# untitled.net
KiCad netlist of a schematic drawn in EAGLE
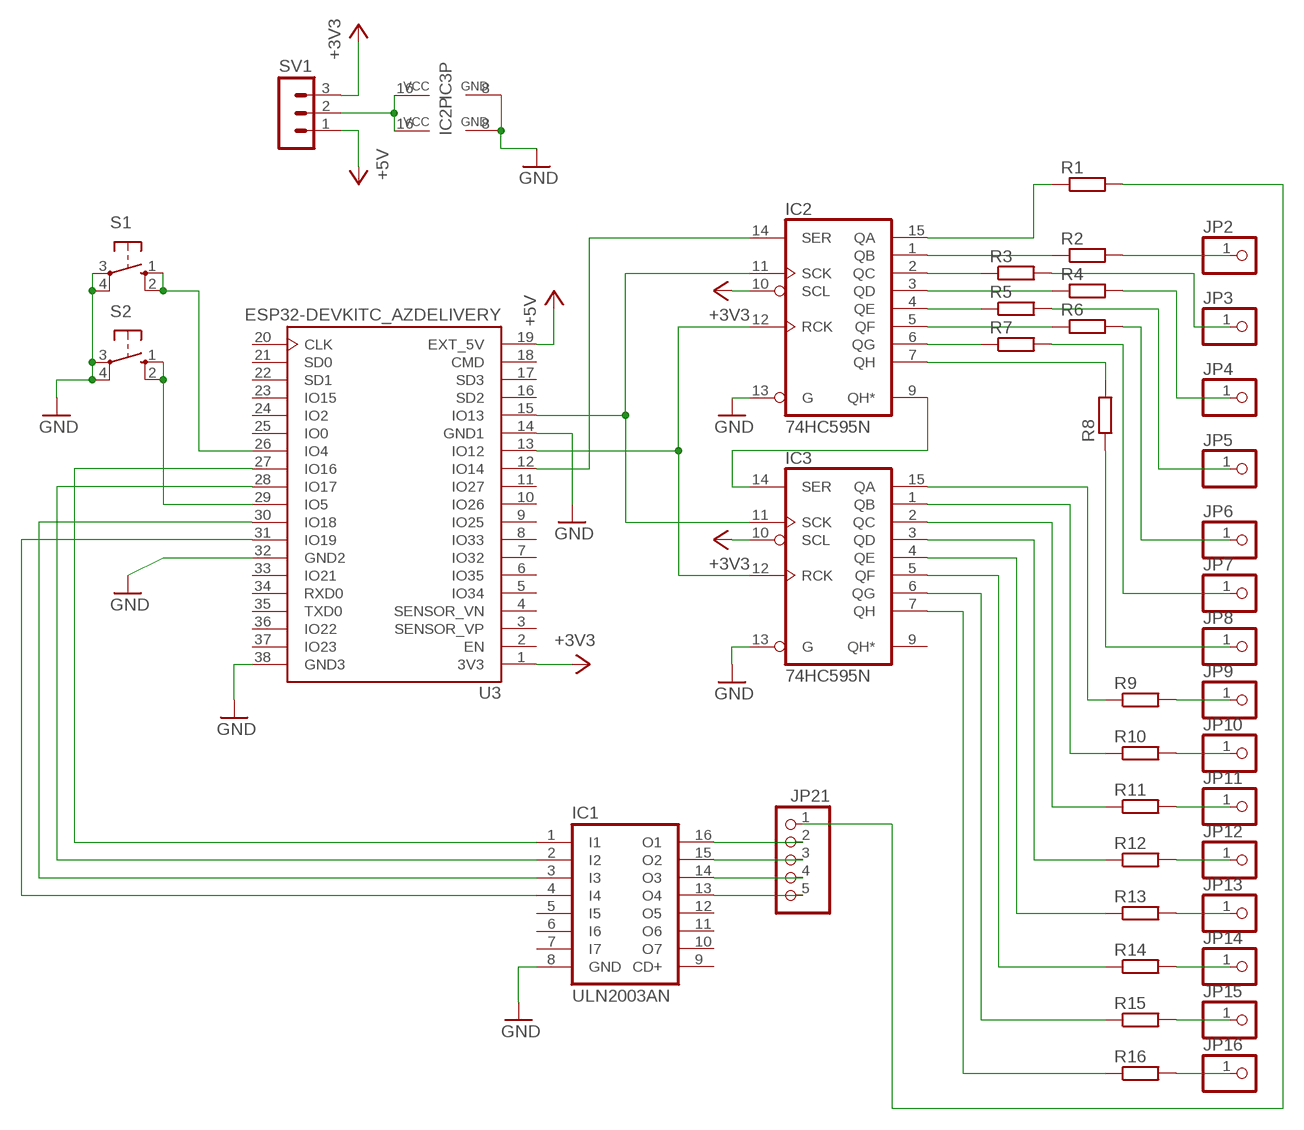
[diagram p0: schematic, sheet 1]

(export (version "E")
  (design (tool "Eeschema 10.0.6"))
  (components
    (comp (ref "IC1")
      (value "ULN2003AN")
      (footprint "eagle-import:DIL16")
      (libsource (lib "eagle-import") (part "ULN2003AN"))
    )
    (comp (ref "IC2")
      (value "74HC595N")
      (footprint "eagle-import:DIL16")
      (libsource (lib "eagle-import") (part "74595NHC"))
    )
    (comp (ref "IC3")
      (value "74HC595N")
      (footprint "eagle-import:DIL16")
      (libsource (lib "eagle-import") (part "74595NHC"))
    )
    (comp (ref "JP2")
      (value "PINHD-1X1")
      (footprint "eagle-import:1X01")
      (libsource (lib "eagle-import") (part "PINHD-1X1"))
    )
    (comp (ref "JP3")
      (value "PINHD-1X1")
      (footprint "eagle-import:1X01")
      (libsource (lib "eagle-import") (part "PINHD-1X1"))
    )
    (comp (ref "JP4")
      (value "PINHD-1X1")
      (footprint "eagle-import:1X01")
      (libsource (lib "eagle-import") (part "PINHD-1X1"))
    )
    (comp (ref "JP5")
      (value "PINHD-1X1")
      (footprint "eagle-import:1X01")
      (libsource (lib "eagle-import") (part "PINHD-1X1"))
    )
    (comp (ref "JP6")
      (value "PINHD-1X1")
      (footprint "eagle-import:1X01")
      (libsource (lib "eagle-import") (part "PINHD-1X1"))
    )
    (comp (ref "JP7")
      (value "PINHD-1X1")
      (footprint "eagle-import:1X01")
      (libsource (lib "eagle-import") (part "PINHD-1X1"))
    )
    (comp (ref "JP8")
      (value "PINHD-1X1")
      (footprint "eagle-import:1X01")
      (libsource (lib "eagle-import") (part "PINHD-1X1"))
    )
    (comp (ref "JP9")
      (value "PINHD-1X1")
      (footprint "eagle-import:1X01")
      (libsource (lib "eagle-import") (part "PINHD-1X1"))
    )
    (comp (ref "JP10")
      (value "PINHD-1X1")
      (footprint "eagle-import:1X01")
      (libsource (lib "eagle-import") (part "PINHD-1X1"))
    )
    (comp (ref "JP11")
      (value "PINHD-1X1")
      (footprint "eagle-import:1X01")
      (libsource (lib "eagle-import") (part "PINHD-1X1"))
    )
    (comp (ref "JP12")
      (value "PINHD-1X1")
      (footprint "eagle-import:1X01")
      (libsource (lib "eagle-import") (part "PINHD-1X1"))
    )
    (comp (ref "JP13")
      (value "PINHD-1X1")
      (footprint "eagle-import:1X01")
      (libsource (lib "eagle-import") (part "PINHD-1X1"))
    )
    (comp (ref "JP14")
      (value "PINHD-1X1")
      (footprint "eagle-import:1X01")
      (libsource (lib "eagle-import") (part "PINHD-1X1"))
    )
    (comp (ref "JP15")
      (value "PINHD-1X1")
      (footprint "eagle-import:1X01")
      (libsource (lib "eagle-import") (part "PINHD-1X1"))
    )
    (comp (ref "JP16")
      (value "PINHD-1X1")
      (footprint "eagle-import:1X01")
      (libsource (lib "eagle-import") (part "PINHD-1X1"))
    )
    (comp (ref "JP21")
      (value "PINHD-1X5")
      (footprint "eagle-import:1X05")
      (libsource (lib "eagle-import") (part "PINHD-1X5"))
    )
    (comp (ref "R1")
      (value "R-EU_0207/10")
      (footprint "eagle-import:0207_10")
      (libsource (lib "eagle-import") (part "R-EU_0207/10"))
    )
    (comp (ref "R2")
      (value "R-EU_0207/10")
      (footprint "eagle-import:0207_10")
      (libsource (lib "eagle-import") (part "R-EU_0207/10"))
    )
    (comp (ref "R3")
      (value "R-EU_0207/10")
      (footprint "eagle-import:0207_10")
      (libsource (lib "eagle-import") (part "R-EU_0207/10"))
    )
    (comp (ref "R4")
      (value "R-EU_0207/10")
      (footprint "eagle-import:0207_10")
      (libsource (lib "eagle-import") (part "R-EU_0207/10"))
    )
    (comp (ref "R5")
      (value "R-EU_0207/10")
      (footprint "eagle-import:0207_10")
      (libsource (lib "eagle-import") (part "R-EU_0207/10"))
    )
    (comp (ref "R6")
      (value "R-EU_0207/10")
      (footprint "eagle-import:0207_10")
      (libsource (lib "eagle-import") (part "R-EU_0207/10"))
    )
    (comp (ref "R7")
      (value "R-EU_0207/10")
      (footprint "eagle-import:0207_10")
      (libsource (lib "eagle-import") (part "R-EU_0207/10"))
    )
    (comp (ref "R8")
      (value "R-EU_0207/10")
      (footprint "eagle-import:0207_10")
      (libsource (lib "eagle-import") (part "R-EU_0207/10"))
    )
    (comp (ref "R9")
      (value "R-EU_0207/10")
      (footprint "eagle-import:0207_10")
      (libsource (lib "eagle-import") (part "R-EU_0207/10"))
    )
    (comp (ref "R10")
      (value "R-EU_0207/10")
      (footprint "eagle-import:0207_10")
      (libsource (lib "eagle-import") (part "R-EU_0207/10"))
    )
    (comp (ref "R11")
      (value "R-EU_0207/10")
      (footprint "eagle-import:0207_10")
      (libsource (lib "eagle-import") (part "R-EU_0207/10"))
    )
    (comp (ref "R12")
      (value "R-EU_0207/10")
      (footprint "eagle-import:0207_10")
      (libsource (lib "eagle-import") (part "R-EU_0207/10"))
    )
    (comp (ref "R13")
      (value "R-EU_0207/10")
      (footprint "eagle-import:0207_10")
      (libsource (lib "eagle-import") (part "R-EU_0207/10"))
    )
    (comp (ref "R14")
      (value "R-EU_0207/10")
      (footprint "eagle-import:0207_10")
      (libsource (lib "eagle-import") (part "R-EU_0207/10"))
    )
    (comp (ref "R15")
      (value "R-EU_0207/10")
      (footprint "eagle-import:0207_10")
      (libsource (lib "eagle-import") (part "R-EU_0207/10"))
    )
    (comp (ref "R16")
      (value "R-EU_0207/10")
      (footprint "eagle-import:0207_10")
      (libsource (lib "eagle-import") (part "R-EU_0207/10"))
    )
    (comp (ref "S1")
      (value "10-XX")
      (footprint "eagle-import:B3F-10XX")
      (fields (field (name "MPN") "B3F-1000"))
      (libsource (lib "eagle-import") (part "10-XX"))
    )
    (comp (ref "S2")
      (value "10-XX")
      (footprint "eagle-import:B3F-10XX")
      (fields (field (name "MPN") "B3F-1000"))
      (libsource (lib "eagle-import") (part "10-XX"))
    )
    (comp (ref "SV1")
      (value "MA03-1")
      (footprint "eagle-import:MA03-1")
      (libsource (lib "eagle-import") (part "MA03-1"))
    )
    (comp (ref "U3")
      (value "ESP32-DEVKITC_AZDELIVERY")
      (footprint "eagle-import:FP_ESP32-DEVKIT_AZDELIVERY")
      (fields (field (name "MF") "Espressif Systems") (field (name "MP") "ESP32-DEVKITC-32D"))
      (libsource (lib "eagle-import") (part "ESP32-DEVKITC_AZDELIVERY"))
    )
  )
  (nets
    (net (code "1") (name "+3V3") (class "Default")
      (node (ref "IC2") (pin "10") (pinfunction "SCL_10") (pintype "input"))
      (node (ref "IC3") (pin "10") (pinfunction "SCL_10") (pintype "input"))
      (node (ref "SV1") (pin "3") (pinfunction "3_3") (pintype "passive"))
      (node (ref "U3") (pin "1") (pinfunction "3V3_1") (pintype "power_in"))
    )
    (net (code "2") (name "+5V") (class "Default")
      (node (ref "SV1") (pin "1") (pinfunction "1_1") (pintype "passive"))
      (node (ref "U3") (pin "19") (pinfunction "EXT_5V_19") (pintype "power_in"))
    )
    (net (code "3") (name "GND") (class "Default")
      (node (ref "IC1") (pin "8") (pinfunction "GND_8") (pintype "power_in"))
      (node (ref "IC2") (pin "13") (pinfunction "G_13") (pintype "input"))
      (node (ref "IC2") (pin "8") (pinfunction "GND_8") (pintype "power_in"))
      (node (ref "IC3") (pin "13") (pinfunction "G_13") (pintype "input"))
      (node (ref "IC3") (pin "8") (pinfunction "GND_8") (pintype "power_in"))
      (node (ref "S1") (pin "3") (pinfunction "P_3") (pintype "passive"))
      (node (ref "S1") (pin "4") (pinfunction "P1_4") (pintype "passive"))
      (node (ref "S2") (pin "3") (pinfunction "P_3") (pintype "passive"))
      (node (ref "S2") (pin "4") (pinfunction "P1_4") (pintype "passive"))
      (node (ref "U3") (pin "14") (pinfunction "GND1_14") (pintype "power_in"))
      (node (ref "U3") (pin "32") (pinfunction "GND2_32") (pintype "power_in"))
      (node (ref "U3") (pin "38") (pinfunction "GND3_38") (pintype "power_in"))
    )
    (net (code "4") (name "Net-(IC1-I1)") (class "Default")
      (node (ref "IC1") (pin "1") (pinfunction "I1_1") (pintype "input"))
      (node (ref "U3") (pin "27") (pinfunction "IO16_27") (pintype "bidirectional"))
    )
    (net (code "5") (name "Net-(IC1-I2)") (class "Default")
      (node (ref "IC1") (pin "2") (pinfunction "I2_2") (pintype "input"))
      (node (ref "U3") (pin "28") (pinfunction "IO17_28") (pintype "bidirectional"))
    )
    (net (code "6") (name "Net-(IC1-I3)") (class "Default")
      (node (ref "IC1") (pin "3") (pinfunction "I3_3") (pintype "input"))
      (node (ref "U3") (pin "30") (pinfunction "IO18_30") (pintype "bidirectional"))
    )
    (net (code "7") (name "Net-(IC1-I4)") (class "Default")
      (node (ref "IC1") (pin "4") (pinfunction "I4_4") (pintype "input"))
      (node (ref "U3") (pin "31") (pinfunction "IO19_31") (pintype "bidirectional"))
    )
    (net (code "8") (name "Net-(IC1-O1)") (class "Default")
      (node (ref "IC1") (pin "16") (pinfunction "O1_16") (pintype "open_collector"))
      (node (ref "JP21") (pin "2") (pinfunction "2_2") (pintype "passive"))
    )
    (net (code "9") (name "Net-(IC1-O2)") (class "Default")
      (node (ref "IC1") (pin "15") (pinfunction "O2_15") (pintype "open_collector"))
      (node (ref "JP21") (pin "3") (pinfunction "3_3") (pintype "passive"))
    )
    (net (code "10") (name "Net-(IC1-O3)") (class "Default")
      (node (ref "IC1") (pin "14") (pinfunction "O3_14") (pintype "open_collector"))
      (node (ref "JP21") (pin "4") (pinfunction "4_4") (pintype "passive"))
    )
    (net (code "11") (name "Net-(IC1-O4)") (class "Default")
      (node (ref "IC1") (pin "13") (pinfunction "O4_13") (pintype "open_collector"))
      (node (ref "JP21") (pin "5") (pinfunction "5_5") (pintype "passive"))
    )
    (net (code "12") (name "Net-(IC2A-QA)") (class "Default")
      (node (ref "IC2") (pin "15") (pinfunction "QA_15") (pintype "tri_state"))
      (node (ref "R1") (pin "1") (pinfunction "1_1") (pintype "passive"))
    )
    (net (code "13") (name "Net-(IC2A-QB)") (class "Default")
      (node (ref "IC2") (pin "1") (pinfunction "QB_1") (pintype "tri_state"))
      (node (ref "R2") (pin "1") (pinfunction "1_1") (pintype "passive"))
    )
    (net (code "14") (name "Net-(IC2A-QC)") (class "Default")
      (node (ref "IC2") (pin "2") (pinfunction "QC_2") (pintype "tri_state"))
      (node (ref "R3") (pin "1") (pinfunction "1_1") (pintype "passive"))
    )
    (net (code "15") (name "Net-(IC2A-QD)") (class "Default")
      (node (ref "IC2") (pin "3") (pinfunction "QD_3") (pintype "tri_state"))
      (node (ref "R4") (pin "1") (pinfunction "1_1") (pintype "passive"))
    )
    (net (code "16") (name "Net-(IC2A-QE)") (class "Default")
      (node (ref "IC2") (pin "4") (pinfunction "QE_4") (pintype "tri_state"))
      (node (ref "R5") (pin "1") (pinfunction "1_1") (pintype "passive"))
    )
    (net (code "17") (name "Net-(IC2A-QF)") (class "Default")
      (node (ref "IC2") (pin "5") (pinfunction "QF_5") (pintype "tri_state"))
      (node (ref "R6") (pin "1") (pinfunction "1_1") (pintype "passive"))
    )
    (net (code "18") (name "Net-(IC2A-QG)") (class "Default")
      (node (ref "IC2") (pin "6") (pinfunction "QG_6") (pintype "tri_state"))
      (node (ref "R7") (pin "1") (pinfunction "1_1") (pintype "passive"))
    )
    (net (code "19") (name "Net-(IC2A-QH)") (class "Default")
      (node (ref "IC2") (pin "7") (pinfunction "QH_7") (pintype "tri_state"))
      (node (ref "R8") (pin "2") (pinfunction "2_2") (pintype "passive"))
    )
    (net (code "20") (name "Net-(IC2A-QH*)") (class "Default")
      (node (ref "IC2") (pin "9") (pinfunction "QH*_9") (pintype "tri_state"))
      (node (ref "IC3") (pin "14") (pinfunction "SER_14") (pintype "input"))
    )
    (net (code "21") (name "Net-(IC2A-RCK)") (class "Default")
      (node (ref "IC2") (pin "12") (pinfunction "RCK_12") (pintype "input"))
      (node (ref "IC3") (pin "12") (pinfunction "RCK_12") (pintype "input"))
      (node (ref "U3") (pin "13") (pinfunction "IO12_13") (pintype "bidirectional"))
    )
    (net (code "22") (name "Net-(IC2A-SCK)") (class "Default")
      (node (ref "IC2") (pin "11") (pinfunction "SCK_11") (pintype "input"))
      (node (ref "IC3") (pin "11") (pinfunction "SCK_11") (pintype "input"))
      (node (ref "U3") (pin "15") (pinfunction "IO13_15") (pintype "bidirectional"))
    )
    (net (code "23") (name "Net-(IC2A-SER)") (class "Default")
      (node (ref "IC2") (pin "14") (pinfunction "SER_14") (pintype "input"))
      (node (ref "U3") (pin "12") (pinfunction "IO14_12") (pintype "bidirectional"))
    )
    (net (code "24") (name "Net-(IC2B-VCC)") (class "Default")
      (node (ref "IC2") (pin "16") (pinfunction "VCC_16") (pintype "power_in"))
      (node (ref "IC3") (pin "16") (pinfunction "VCC_16") (pintype "power_in"))
      (node (ref "SV1") (pin "2") (pinfunction "2_2") (pintype "passive"))
    )
    (net (code "25") (name "Net-(IC3A-QA)") (class "Default")
      (node (ref "IC3") (pin "15") (pinfunction "QA_15") (pintype "tri_state"))
      (node (ref "R9") (pin "1") (pinfunction "1_1") (pintype "passive"))
    )
    (net (code "26") (name "Net-(IC3A-QB)") (class "Default")
      (node (ref "IC3") (pin "1") (pinfunction "QB_1") (pintype "tri_state"))
      (node (ref "R10") (pin "1") (pinfunction "1_1") (pintype "passive"))
    )
    (net (code "27") (name "Net-(IC3A-QC)") (class "Default")
      (node (ref "IC3") (pin "2") (pinfunction "QC_2") (pintype "tri_state"))
      (node (ref "R11") (pin "1") (pinfunction "1_1") (pintype "passive"))
    )
    (net (code "28") (name "Net-(IC3A-QD)") (class "Default")
      (node (ref "IC3") (pin "3") (pinfunction "QD_3") (pintype "tri_state"))
      (node (ref "R12") (pin "1") (pinfunction "1_1") (pintype "passive"))
    )
    (net (code "29") (name "Net-(IC3A-QE)") (class "Default")
      (node (ref "IC3") (pin "4") (pinfunction "QE_4") (pintype "tri_state"))
      (node (ref "R13") (pin "1") (pinfunction "1_1") (pintype "passive"))
    )
    (net (code "30") (name "Net-(IC3A-QF)") (class "Default")
      (node (ref "IC3") (pin "5") (pinfunction "QF_5") (pintype "tri_state"))
      (node (ref "R14") (pin "1") (pinfunction "1_1") (pintype "passive"))
    )
    (net (code "31") (name "Net-(IC3A-QG)") (class "Default")
      (node (ref "IC3") (pin "6") (pinfunction "QG_6") (pintype "tri_state"))
      (node (ref "R15") (pin "1") (pinfunction "1_1") (pintype "passive"))
    )
    (net (code "32") (name "Net-(IC3A-QH)") (class "Default")
      (node (ref "IC3") (pin "7") (pinfunction "QH_7") (pintype "tri_state"))
      (node (ref "R16") (pin "1") (pinfunction "1_1") (pintype "passive"))
    )
    (net (code "33") (name "Net-(JP2-Pad1)") (class "Default")
      (node (ref "JP2") (pin "1") (pinfunction "1_1") (pintype "passive"))
      (node (ref "R2") (pin "2") (pinfunction "2_2") (pintype "passive"))
    )
    (net (code "34") (name "Net-(JP3-Pad1)") (class "Default")
      (node (ref "JP3") (pin "1") (pinfunction "1_1") (pintype "passive"))
      (node (ref "R3") (pin "2") (pinfunction "2_2") (pintype "passive"))
    )
    (net (code "35") (name "Net-(JP4-Pad1)") (class "Default")
      (node (ref "JP4") (pin "1") (pinfunction "1_1") (pintype "passive"))
      (node (ref "R4") (pin "2") (pinfunction "2_2") (pintype "passive"))
    )
    (net (code "36") (name "Net-(JP5-Pad1)") (class "Default")
      (node (ref "JP5") (pin "1") (pinfunction "1_1") (pintype "passive"))
      (node (ref "R5") (pin "2") (pinfunction "2_2") (pintype "passive"))
    )
    (net (code "37") (name "Net-(JP6-Pad1)") (class "Default")
      (node (ref "JP6") (pin "1") (pinfunction "1_1") (pintype "passive"))
      (node (ref "R6") (pin "2") (pinfunction "2_2") (pintype "passive"))
    )
    (net (code "38") (name "Net-(JP7-Pad1)") (class "Default")
      (node (ref "JP7") (pin "1") (pinfunction "1_1") (pintype "passive"))
      (node (ref "R7") (pin "2") (pinfunction "2_2") (pintype "passive"))
    )
    (net (code "39") (name "Net-(JP8-Pad1)") (class "Default")
      (node (ref "JP8") (pin "1") (pinfunction "1_1") (pintype "passive"))
      (node (ref "R8") (pin "1") (pinfunction "1_1") (pintype "passive"))
    )
    (net (code "40") (name "Net-(JP9-Pad1)") (class "Default")
      (node (ref "JP9") (pin "1") (pinfunction "1_1") (pintype "passive"))
      (node (ref "R9") (pin "2") (pinfunction "2_2") (pintype "passive"))
    )
    (net (code "41") (name "Net-(JP10-Pad1)") (class "Default")
      (node (ref "JP10") (pin "1") (pinfunction "1_1") (pintype "passive"))
      (node (ref "R10") (pin "2") (pinfunction "2_2") (pintype "passive"))
    )
    (net (code "42") (name "Net-(JP11-Pad1)") (class "Default")
      (node (ref "JP11") (pin "1") (pinfunction "1_1") (pintype "passive"))
      (node (ref "R11") (pin "2") (pinfunction "2_2") (pintype "passive"))
    )
    (net (code "43") (name "Net-(JP12-Pad1)") (class "Default")
      (node (ref "JP12") (pin "1") (pinfunction "1_1") (pintype "passive"))
      (node (ref "R12") (pin "2") (pinfunction "2_2") (pintype "passive"))
    )
    (net (code "44") (name "Net-(JP13-Pad1)") (class "Default")
      (node (ref "JP13") (pin "1") (pinfunction "1_1") (pintype "passive"))
      (node (ref "R13") (pin "2") (pinfunction "2_2") (pintype "passive"))
    )
    (net (code "45") (name "Net-(JP14-Pad1)") (class "Default")
      (node (ref "JP14") (pin "1") (pinfunction "1_1") (pintype "passive"))
      (node (ref "R14") (pin "2") (pinfunction "2_2") (pintype "passive"))
    )
    (net (code "46") (name "Net-(JP15-Pad1)") (class "Default")
      (node (ref "JP15") (pin "1") (pinfunction "1_1") (pintype "passive"))
      (node (ref "R15") (pin "2") (pinfunction "2_2") (pintype "passive"))
    )
    (net (code "47") (name "Net-(JP16-Pad1)") (class "Default")
      (node (ref "JP16") (pin "1") (pinfunction "1_1") (pintype "passive"))
      (node (ref "R16") (pin "2") (pinfunction "2_2") (pintype "passive"))
    )
    (net (code "48") (name "Net-(JP21-Pad1)") (class "Default")
      (node (ref "JP21") (pin "1") (pinfunction "1_1") (pintype "passive"))
      (node (ref "R1") (pin "2") (pinfunction "2_2") (pintype "passive"))
    )
    (net (code "49") (name "Net-(S1-S)") (class "Default")
      (node (ref "S1") (pin "1") (pinfunction "S_1") (pintype "passive"))
      (node (ref "S1") (pin "2") (pinfunction "S1_2") (pintype "passive"))
      (node (ref "U3") (pin "26") (pinfunction "IO4_26") (pintype "bidirectional"))
    )
    (net (code "50") (name "Net-(S2-S)") (class "Default")
      (node (ref "S2") (pin "1") (pinfunction "S_1") (pintype "passive"))
      (node (ref "S2") (pin "2") (pinfunction "S1_2") (pintype "passive"))
      (node (ref "U3") (pin "29") (pinfunction "IO5_29") (pintype "bidirectional"))
    )
    (net (code "51") (name "unconnected-(IC1-CD+-Pad9)") (class "Default")
      (node (ref "IC1") (pin "9") (pinfunction "CD+_9") (pintype "passive"))
    )
    (net (code "52") (name "unconnected-(IC1-I5-Pad5)") (class "Default")
      (node (ref "IC1") (pin "5") (pinfunction "I5_5") (pintype "input"))
    )
    (net (code "53") (name "unconnected-(IC1-I6-Pad6)") (class "Default")
      (node (ref "IC1") (pin "6") (pinfunction "I6_6") (pintype "input"))
    )
    (net (code "54") (name "unconnected-(IC1-I7-Pad7)") (class "Default")
      (node (ref "IC1") (pin "7") (pinfunction "I7_7") (pintype "input"))
    )
    (net (code "55") (name "unconnected-(IC1-O5-Pad12)") (class "Default")
      (node (ref "IC1") (pin "12") (pinfunction "O5_12") (pintype "open_collector"))
    )
    (net (code "56") (name "unconnected-(IC1-O6-Pad11)") (class "Default")
      (node (ref "IC1") (pin "11") (pinfunction "O6_11") (pintype "open_collector"))
    )
    (net (code "57") (name "unconnected-(IC1-O7-Pad10)") (class "Default")
      (node (ref "IC1") (pin "10") (pinfunction "O7_10") (pintype "open_collector"))
    )
    (net (code "58") (name "unconnected-(IC3A-QH*-Pad9)") (class "Default")
      (node (ref "IC3") (pin "9") (pinfunction "QH*_9") (pintype "tri_state"))
    )
    (net (code "59") (name "unconnected-(U3-CLK-Pad20)") (class "Default")
      (node (ref "U3") (pin "20") (pinfunction "CLK_20") (pintype "input"))
    )
    (net (code "60") (name "unconnected-(U3-CMD-Pad18)") (class "Default")
      (node (ref "U3") (pin "18") (pinfunction "CMD_18") (pintype "bidirectional"))
    )
    (net (code "61") (name "unconnected-(U3-EN-Pad2)") (class "Default")
      (node (ref "U3") (pin "2") (pinfunction "EN_2") (pintype "input"))
    )
    (net (code "62") (name "unconnected-(U3-IO0-Pad25)") (class "Default")
      (node (ref "U3") (pin "25") (pinfunction "IO0_25") (pintype "bidirectional"))
    )
    (net (code "63") (name "unconnected-(U3-IO2-Pad24)") (class "Default")
      (node (ref "U3") (pin "24") (pinfunction "IO2_24") (pintype "bidirectional"))
    )
    (net (code "64") (name "unconnected-(U3-IO15-Pad23)") (class "Default")
      (node (ref "U3") (pin "23") (pinfunction "IO15_23") (pintype "bidirectional"))
    )
    (net (code "65") (name "unconnected-(U3-IO21-Pad33)") (class "Default")
      (node (ref "U3") (pin "33") (pinfunction "IO21_33") (pintype "bidirectional"))
    )
    (net (code "66") (name "unconnected-(U3-IO22-Pad36)") (class "Default")
      (node (ref "U3") (pin "36") (pinfunction "IO22_36") (pintype "bidirectional"))
    )
    (net (code "67") (name "unconnected-(U3-IO23-Pad37)") (class "Default")
      (node (ref "U3") (pin "37") (pinfunction "IO23_37") (pintype "bidirectional"))
    )
    (net (code "68") (name "unconnected-(U3-IO25-Pad9)") (class "Default")
      (node (ref "U3") (pin "9") (pinfunction "IO25_9") (pintype "bidirectional"))
    )
    (net (code "69") (name "unconnected-(U3-IO26-Pad10)") (class "Default")
      (node (ref "U3") (pin "10") (pinfunction "IO26_10") (pintype "bidirectional"))
    )
    (net (code "70") (name "unconnected-(U3-IO27-Pad11)") (class "Default")
      (node (ref "U3") (pin "11") (pinfunction "IO27_11") (pintype "bidirectional"))
    )
    (net (code "71") (name "unconnected-(U3-IO32-Pad7)") (class "Default")
      (node (ref "U3") (pin "7") (pinfunction "IO32_7") (pintype "bidirectional"))
    )
    (net (code "72") (name "unconnected-(U3-IO33-Pad8)") (class "Default")
      (node (ref "U3") (pin "8") (pinfunction "IO33_8") (pintype "bidirectional"))
    )
    (net (code "73") (name "unconnected-(U3-IO34-Pad5)") (class "Default")
      (node (ref "U3") (pin "5") (pinfunction "IO34_5") (pintype "bidirectional"))
    )
    (net (code "74") (name "unconnected-(U3-IO35-Pad6)") (class "Default")
      (node (ref "U3") (pin "6") (pinfunction "IO35_6") (pintype "bidirectional"))
    )
    (net (code "75") (name "unconnected-(U3-RXD0-Pad34)") (class "Default")
      (node (ref "U3") (pin "34") (pinfunction "RXD0_34") (pintype "input"))
    )
    (net (code "76") (name "unconnected-(U3-SD0-Pad21)") (class "Default")
      (node (ref "U3") (pin "21") (pinfunction "SD0_21") (pintype "bidirectional"))
    )
    (net (code "77") (name "unconnected-(U3-SD1-Pad22)") (class "Default")
      (node (ref "U3") (pin "22") (pinfunction "SD1_22") (pintype "bidirectional"))
    )
    (net (code "78") (name "unconnected-(U3-SD2-Pad16)") (class "Default")
      (node (ref "U3") (pin "16") (pinfunction "SD2_16") (pintype "bidirectional"))
    )
    (net (code "79") (name "unconnected-(U3-SD3-Pad17)") (class "Default")
      (node (ref "U3") (pin "17") (pinfunction "SD3_17") (pintype "bidirectional"))
    )
    (net (code "80") (name "unconnected-(U3-SENSOR_VN-Pad4)") (class "Default")
      (node (ref "U3") (pin "4") (pinfunction "SENSOR_VN_4") (pintype "input"))
    )
    (net (code "81") (name "unconnected-(U3-SENSOR_VP-Pad3)") (class "Default")
      (node (ref "U3") (pin "3") (pinfunction "SENSOR_VP_3") (pintype "input"))
    )
    (net (code "82") (name "unconnected-(U3-TXD0-Pad35)") (class "Default")
      (node (ref "U3") (pin "35") (pinfunction "TXD0_35") (pintype "output"))
    )
  )
)
